# LitVP-02.net
KiCad netlist of a schematic drawn in Altium Designer
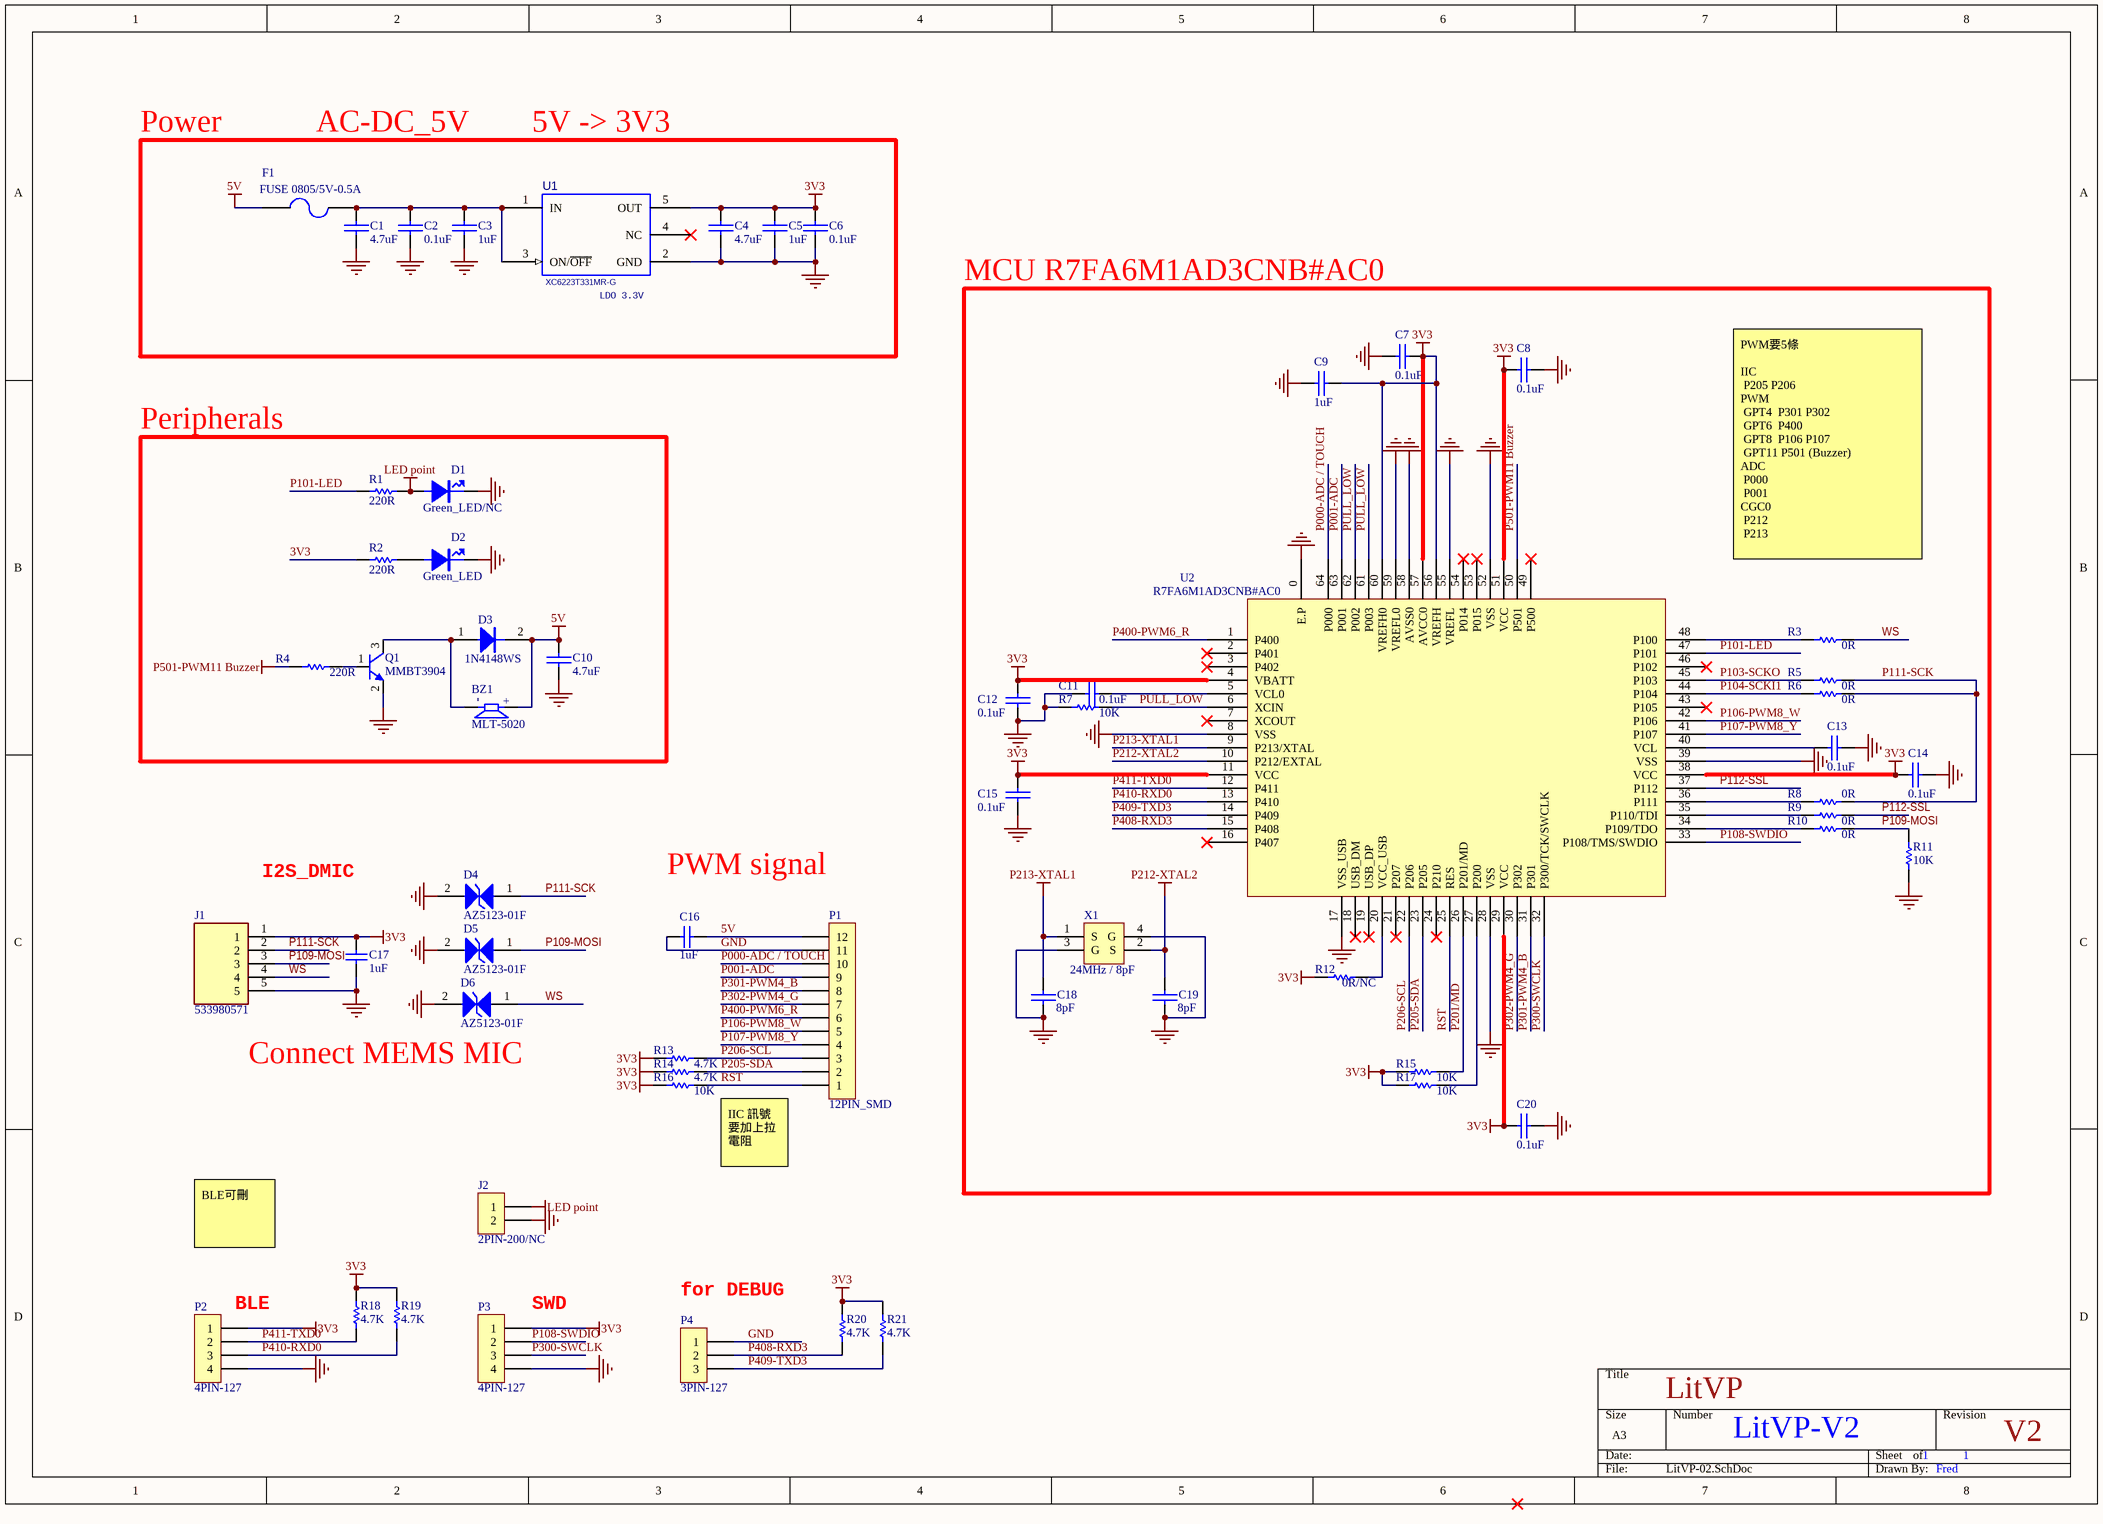
[diagram p0: LitVP-02.SchDoc]

(export (version "E")
  (design (tool "Eeschema 10.0.6"))
  (components
    (comp (ref "BZ1")
      (value "MLT-5020")
      (footprint "BUZZER-SMD-5*5mm")
      (description "Buzzer")
      (libsource (lib "*") (part "YZ5020CS-03L-4.0-12-R"))
    )
    (comp (ref "C1")
      (value "4.7uF")
      (footprint "QUAN:0402C")
      (description "Capacitor")
      (libsource (lib "CAP") (part "CAP"))
    )
    (comp (ref "C2")
      (value "0.1uF")
      (footprint "QUAN:0402C")
      (description "Capacitor")
      (libsource (lib "CAP") (part "CAP"))
    )
    (comp (ref "C3")
      (value "1uF")
      (footprint "QUAN:0402C")
      (description "Capacitor")
      (libsource (lib "CAP") (part "CAP"))
    )
    (comp (ref "C4")
      (value "4.7uF")
      (footprint "QUAN:0402C")
      (description "Capacitor")
      (libsource (lib "CAP") (part "CAP"))
    )
    (comp (ref "C5")
      (value "1uF")
      (footprint "QUAN:0402C")
      (description "Capacitor")
      (libsource (lib "CAP") (part "CAP"))
    )
    (comp (ref "C6")
      (value "0.1uF")
      (footprint "QUAN:0402C")
      (description "Capacitor")
      (libsource (lib "CAP") (part "CAP"))
    )
    (comp (ref "C7")
      (value "0.1uF")
      (footprint "QUAN:0402C")
      (description "Capacitor")
      (libsource (lib "CAP") (part "CAP"))
    )
    (comp (ref "C8")
      (value "0.1uF")
      (footprint "QUAN:0402C")
      (description "Capacitor")
      (libsource (lib "CAP") (part "CAP"))
    )
    (comp (ref "C9")
      (value "1uF")
      (footprint "QUAN:0402C")
      (description "Capacitor")
      (libsource (lib "CAP") (part "CAP"))
    )
    (comp (ref "C10")
      (value "4.7uF")
      (footprint "QUAN:0402C")
      (description "Capacitor")
      (libsource (lib "CAP") (part "CAP"))
    )
    (comp (ref "C11")
      (value "0.1uF")
      (footprint "QUAN:0402C")
      (description "Capacitor")
      (libsource (lib "CAP") (part "CAP"))
    )
    (comp (ref "C12")
      (value "0.1uF")
      (footprint "QUAN:0402C")
      (description "Capacitor")
      (libsource (lib "CAP") (part "CAP"))
    )
    (comp (ref "C13")
      (value "0.1uF")
      (footprint "QUAN:0402C")
      (description "Capacitor")
      (libsource (lib "CAP") (part "CAP"))
    )
    (comp (ref "C14")
      (value "0.1uF")
      (footprint "QUAN:0402C")
      (description "Capacitor")
      (libsource (lib "CAP") (part "CAP"))
    )
    (comp (ref "C15")
      (value "0.1uF")
      (footprint "QUAN:0402C")
      (description "Capacitor")
      (libsource (lib "CAP") (part "CAP"))
    )
    (comp (ref "C16")
      (value "1uF")
      (footprint "QUAN:0402C")
      (description "Capacitor")
      (libsource (lib "*") (part "Cap Semi"))
    )
    (comp (ref "C17")
      (value "1uF")
      (footprint "QUAN:0402C")
      (description "Capacitor")
      (libsource (lib "*") (part "Cap Semi"))
    )
    (comp (ref "C18")
      (value "8pF")
      (footprint "QUAN:0402C")
      (description "Capacitor")
      (libsource (lib "*") (part "CAP"))
    )
    (comp (ref "C19")
      (value "8pF")
      (footprint "QUAN:0402C")
      (description "Capacitor")
      (libsource (lib "*") (part "CAP"))
    )
    (comp (ref "C20")
      (value "0.1uF")
      (footprint "QUAN:0402C")
      (description "Capacitor")
      (libsource (lib "CAP") (part "CAP"))
    )
    (comp (ref "D1")
      (value "Green_LED/NC")
      (footprint "LED0603--0.4mm")
      (fields
        (field (name "MANUFACTURER'S PART NUMBER") "CL-170G-CD-T")
        (field (name "PART NUMBER") "41100017000")
        (field (name "MANUFACTURER") "Citizen")
      )
      (libsource (lib "*") (part "LED"))
    )
    (comp (ref "D2")
      (value "Green_LED")
      (footprint "LED0603--0.4mm")
      (fields
        (field (name "MANUFACTURER'S PART NUMBER") "CL-170G-CD-T")
        (field (name "PART NUMBER") "41100017000")
        (field (name "MANUFACTURER") "Citizen")
      )
      (libsource (lib "*") (part "LED"))
    )
    (comp (ref "D3")
      (value "1N4148WS")
      (footprint "SOD323-1N4148WS - pig pad")
      (libsource (lib "*") (part "DIODE"))
    )
    (comp (ref "D4")
      (value "AZ5123-01F")
      (footprint "LitVP-02:DIODE-0402")
      (description "ESD")
      (libsource (lib "*") (part "PESD5V0L1BA"))
    )
    (comp (ref "D5")
      (value "AZ5123-01F")
      (footprint "DIODE-0402")
      (description "ESD")
      (libsource (lib "*") (part "PESD5V0L1BA"))
    )
    (comp (ref "D6")
      (value "AZ5123-01F")
      (footprint "DIODE-0402")
      (description "ESD")
      (libsource (lib "*") (part "PESD5V0L1BA"))
    )
    (comp (ref "F1")
      (value "FUSE 0805/5V-0.5A")
      (footprint "QUAN:0805_FUSE")
      (description "Fuse")
      (libsource (lib "*") (part "FUSE2"))
    )
    (comp (ref "J1")
      (value "533980571")
      (footprint "SamacSys:53398-0571")
      (description "Connector")
      (fields (field (name "MANUFACTURER_PART_NUMBER") "53048-0510"))
      (libsource (lib "*") (part "53048-0510"))
    )
    (comp (ref "J2")
      (value "2PIN-200/NC")
      (footprint "2PIN-127")
      (description "Connector")
      (libsource (lib "PIN") (part "2PIN-200"))
    )
    (comp (ref "P1")
      (value "12PIN_SMD")
      (footprint "QUAN:12PIN_SAMTEC-MMT-136-02-X-SH")
      (libsource (lib "PIN") (part "12PIN_SMD"))
    )
    (comp (ref "P2")
      (value "4PIN-127")
      (footprint "QUAN:4PIN-127_0.85_0.505")
      (description "1.27mm Header")
      (libsource (lib "*") (part "CON4"))
    )
    (comp (ref "P3")
      (value "4PIN-127")
      (footprint "QUAN:4PIN-127_0.85_0.505")
      (description "1.27mm Header")
      (libsource (lib "*") (part "CON4"))
    )
    (comp (ref "P4") (value "3PIN-127") (footprint "QUAN:3PIN-127") (libsource (lib "PIN") (part "3PIN-127")))
    (comp (ref "Q1")
      (value "MMBT3904")
      (footprint "QUAN:SOT-23")
      (description "NPN General Purpose Amplifier")
      (fields (field (name "PUBLISHER") "*"))
      (libsource (lib "*") (part "NPN-3"))
    )
    (comp (ref "R1")
      (value "220R")
      (footprint "QUAN:0402")
      (description "Resistor")
      (libsource (lib "*") (part "Res Semi"))
    )
    (comp (ref "R2")
      (value "220R")
      (footprint "QUAN:0402")
      (description "Resistor")
      (libsource (lib "*") (part "Res Semi"))
    )
    (comp (ref "R3")
      (value "0R")
      (footprint "QUAN:0402")
      (description "Resistor")
      (libsource (lib "*") (part "Res Semi"))
    )
    (comp (ref "R4")
      (value "220R")
      (footprint "QUAN:0402")
      (description "Resistor")
      (libsource (lib "*") (part "Res Semi"))
    )
    (comp (ref "R5")
      (value "0R")
      (footprint "QUAN:0402")
      (description "Resistor")
      (libsource (lib "*") (part "Res Semi"))
    )
    (comp (ref "R6")
      (value "0R")
      (footprint "QUAN:0402")
      (description "Resistor")
      (libsource (lib "*") (part "Res Semi"))
    )
    (comp (ref "R7")
      (value "10K")
      (footprint "QUAN:0402")
      (description "Resistor")
      (libsource (lib "*") (part "Res Semi"))
    )
    (comp (ref "R8")
      (value "0R")
      (footprint "QUAN:0402")
      (description "Resistor")
      (libsource (lib "*") (part "Res Semi"))
    )
    (comp (ref "R9")
      (value "0R")
      (footprint "QUAN:0402")
      (description "Resistor")
      (libsource (lib "*") (part "Res Semi"))
    )
    (comp (ref "R10")
      (value "0R")
      (footprint "QUAN:0402")
      (description "Resistor")
      (libsource (lib "*") (part "Res Semi"))
    )
    (comp (ref "R11")
      (value "10K")
      (footprint "QUAN:0402")
      (description "Resistor")
      (libsource (lib "*") (part "Res Semi"))
    )
    (comp (ref "R12")
      (value "0R/NC")
      (footprint "QUAN:0402")
      (description "Resistor")
      (libsource (lib "*") (part "Res Semi"))
    )
    (comp (ref "R13")
      (value "4.7K")
      (footprint "QUAN:0402")
      (description "Resistor")
      (libsource (lib "*") (part "Res Semi"))
    )
    (comp (ref "R14")
      (value "4.7K")
      (footprint "QUAN:0402")
      (description "Resistor")
      (libsource (lib "*") (part "Res Semi"))
    )
    (comp (ref "R15")
      (value "10K")
      (footprint "QUAN:0402")
      (description "Resistor")
      (libsource (lib "*") (part "Res Semi"))
    )
    (comp (ref "R16")
      (value "10K")
      (footprint "QUAN:0402")
      (description "Resistor")
      (libsource (lib "*") (part "Res Semi"))
    )
    (comp (ref "R17")
      (value "10K")
      (footprint "QUAN:0402")
      (description "Resistor")
      (libsource (lib "*") (part "Res Semi"))
    )
    (comp (ref "R18")
      (value "4.7K")
      (footprint "QUAN:0402")
      (description "Resistor")
      (libsource (lib "*") (part "Res Semi"))
    )
    (comp (ref "R19")
      (value "4.7K")
      (footprint "QUAN:0402")
      (description "Resistor")
      (libsource (lib "*") (part "Res Semi"))
    )
    (comp (ref "R20")
      (value "4.7K")
      (footprint "QUAN:0402")
      (description "Resistor")
      (libsource (lib "*") (part "Res Semi"))
    )
    (comp (ref "R21")
      (value "4.7K")
      (footprint "QUAN:0402")
      (description "Resistor")
      (libsource (lib "*") (part "Res Semi"))
    )
    (comp (ref "U1")
      (value "XC6223T331MR-G")
      (footprint "SOT-23-5-0.95MM")
      (libsource (lib "*") (part "XC6223T331MR-G"))
    )
    (comp (ref "U2")
      (value "R7FA6M1AD3CNB#AC0")
      (footprint "QFN64-0.4mm-8X8")
      (description "MCU")
      (libsource (lib "*") (part "R7FA6M1AD3CNB#AC0"))
    )
    (comp (ref "X1")
      (value "24MHz / 8pF")
      (footprint "XTAL-SMD-20X16")
      (libsource (lib "*") (part "XTAL-SMD-25*32"))
    )
  )
  (nets
    (net (code "1") (name "/P000-ADC {slash} TOUCH") (class "Default")
      (node (ref "P1") (pin "10") (pinfunction "10_10") (pintype "passive"))
      (node (ref "U2") (pin "64") (pinfunction "P000_64") (pintype "passive"))
    )
    (net (code "2") (name "/P001-ADC") (class "Default")
      (node (ref "P1") (pin "9") (pinfunction "9_9") (pintype "passive"))
      (node (ref "U2") (pin "63") (pinfunction "P001_63") (pintype "passive"))
    )
    (net (code "3") (name "/P101-LED") (class "Default")
      (node (ref "R1") (pin "1") (pinfunction "1_1") (pintype "passive"))
      (node (ref "U2") (pin "47") (pinfunction "P101_47") (pintype "passive"))
    )
    (net (code "4") (name "/P103-SCKO") (class "Default")
      (node (ref "R5") (pin "2") (pinfunction "2_2") (pintype "passive"))
      (node (ref "U2") (pin "45") (pinfunction "P103_45") (pintype "passive"))
    )
    (net (code "5") (name "/P104-SCKI1") (class "Default")
      (node (ref "R6") (pin "2") (pinfunction "2_2") (pintype "passive"))
      (node (ref "U2") (pin "44") (pinfunction "P104_44") (pintype "passive"))
    )
    (net (code "6") (name "/P106-PWM8_W") (class "Default")
      (node (ref "P1") (pin "5") (pinfunction "5_5") (pintype "passive"))
      (node (ref "U2") (pin "42") (pinfunction "P106_42") (pintype "passive"))
    )
    (net (code "7") (name "/P107-PWM8_Y") (class "Default")
      (node (ref "P1") (pin "4") (pinfunction "4_4") (pintype "passive"))
      (node (ref "U2") (pin "41") (pinfunction "P107_41") (pintype "passive"))
    )
    (net (code "8") (name "/P108-SWDIO") (class "Default")
      (node (ref "P3") (pin "2") (pinfunction "2_2") (pintype "passive"))
      (node (ref "U2") (pin "33") (pinfunction "P108/TMS/SWDIO_33") (pintype "passive"))
    )
    (net (code "9") (name "/P109-MOSI") (class "Default")
      (node (ref "D5") (pin "1") (pinfunction "1_1") (pintype "passive"))
      (node (ref "J1") (pin "3") (pinfunction "3_3") (pintype "passive"))
      (node (ref "R10") (pin "1") (pinfunction "1_1") (pintype "passive"))
      (node (ref "R11") (pin "2") (pinfunction "2_2") (pintype "passive"))
    )
    (net (code "10") (name "/P111-SCK") (class "Default")
      (node (ref "D4") (pin "1") (pinfunction "1_1") (pintype "passive"))
      (node (ref "J1") (pin "2") (pinfunction "2_2") (pintype "passive"))
      (node (ref "R5") (pin "1") (pinfunction "1_1") (pintype "passive"))
      (node (ref "R6") (pin "1") (pinfunction "1_1") (pintype "passive"))
      (node (ref "R8") (pin "1") (pinfunction "1_1") (pintype "passive"))
    )
    (net (code "11") (name "/P112-SSL") (class "Default")
      (node (ref "R9") (pin "1") (pinfunction "1_1") (pintype "passive"))
      (node (ref "U2") (pin "37") (pinfunction "P112_37") (pintype "passive"))
    )
    (net (code "12") (name "/P201{slash}MD") (class "Default")
      (node (ref "R15") (pin "1") (pinfunction "1_1") (pintype "passive"))
      (node (ref "U2") (pin "26") (pinfunction "P201/MD_26") (pintype "passive"))
    )
    (net (code "13") (name "/P205-SDA") (class "Default")
      (node (ref "P1") (pin "2") (pinfunction "2_2") (pintype "passive"))
      (node (ref "R14") (pin "1") (pinfunction "1_1") (pintype "passive"))
      (node (ref "U2") (pin "23") (pinfunction "P205_23") (pintype "passive"))
    )
    (net (code "14") (name "/P206-SCL") (class "Default")
      (node (ref "P1") (pin "3") (pinfunction "3_3") (pintype "passive"))
      (node (ref "R13") (pin "1") (pinfunction "1_1") (pintype "passive"))
      (node (ref "U2") (pin "22") (pinfunction "P206_22") (pintype "passive"))
    )
    (net (code "15") (name "/P300-SWCLK") (class "Default")
      (node (ref "P3") (pin "3") (pinfunction "3_3") (pintype "passive"))
      (node (ref "U2") (pin "32") (pinfunction "P300/TCK/SWCLK_32") (pintype "passive"))
    )
    (net (code "16") (name "/P301-PWM4_B") (class "Default")
      (node (ref "P1") (pin "8") (pinfunction "8_8") (pintype "passive"))
      (node (ref "U2") (pin "31") (pinfunction "P301_31") (pintype "passive"))
    )
    (net (code "17") (name "/P302-PWM4_G") (class "Default")
      (node (ref "P1") (pin "7") (pinfunction "7_7") (pintype "passive"))
      (node (ref "U2") (pin "30") (pinfunction "P302_30") (pintype "passive"))
    )
    (net (code "18") (name "/P400-PWM6_R") (class "Default")
      (node (ref "P1") (pin "6") (pinfunction "6_6") (pintype "passive"))
      (node (ref "U2") (pin "1") (pinfunction "P400_1") (pintype "passive"))
    )
    (net (code "19") (name "/P408-RXD3") (class "Default")
      (node (ref "P4") (pin "2") (pinfunction "2_2") (pintype "passive"))
      (node (ref "R20") (pin "2") (pinfunction "2_2") (pintype "passive"))
      (node (ref "U2") (pin "15") (pinfunction "P408_15") (pintype "passive"))
    )
    (net (code "20") (name "/P409-TXD3") (class "Default")
      (node (ref "P4") (pin "3") (pinfunction "3_3") (pintype "passive"))
      (node (ref "R21") (pin "2") (pinfunction "2_2") (pintype "passive"))
      (node (ref "U2") (pin "14") (pinfunction "P409_14") (pintype "passive"))
    )
    (net (code "21") (name "/P410-RXD0") (class "Default")
      (node (ref "P2") (pin "3") (pinfunction "3_3") (pintype "passive"))
      (node (ref "R19") (pin "2") (pinfunction "2_2") (pintype "passive"))
      (node (ref "U2") (pin "13") (pinfunction "P410_13") (pintype "passive"))
    )
    (net (code "22") (name "/P411-TXD0") (class "Default")
      (node (ref "P2") (pin "2") (pinfunction "2_2") (pintype "passive"))
      (node (ref "R18") (pin "2") (pinfunction "2_2") (pintype "passive"))
      (node (ref "U2") (pin "12") (pinfunction "P411_12") (pintype "passive"))
    )
    (net (code "23") (name "/PULL_LOW") (class "Default")
      (node (ref "R7") (pin "1") (pinfunction "1_1") (pintype "passive"))
      (node (ref "U2") (pin "6") (pinfunction "XCIN_6") (pintype "passive"))
      (node (ref "U2") (pin "61") (pinfunction "P003_61") (pintype "passive"))
      (node (ref "U2") (pin "62") (pinfunction "P002_62") (pintype "passive"))
    )
    (net (code "24") (name "/RST") (class "Default")
      (node (ref "P1") (pin "1") (pinfunction "1_1") (pintype "passive"))
      (node (ref "R16") (pin "1") (pinfunction "1_1") (pintype "passive"))
      (node (ref "U2") (pin "25") (pinfunction "RES_25") (pintype "passive"))
    )
    (net (code "25") (name "/WS") (class "Default")
      (node (ref "D6") (pin "1") (pinfunction "1_1") (pintype "passive"))
      (node (ref "J1") (pin "4") (pinfunction "4_4") (pintype "passive"))
      (node (ref "R3") (pin "1") (pinfunction "1_1") (pintype "passive"))
    )
    (net (code "26") (name "3V3") (class "Default")
      (node (ref "C12") (pin "2") (pinfunction "2_2") (pintype "passive"))
      (node (ref "C14") (pin "2") (pinfunction "2_2") (pintype "passive"))
      (node (ref "C15") (pin "2") (pinfunction "2_2") (pintype "passive"))
      (node (ref "C17") (pin "2") (pinfunction "2_2") (pintype "passive"))
      (node (ref "C20") (pin "2") (pinfunction "2_2") (pintype "passive"))
      (node (ref "C4") (pin "1") (pinfunction "1_1") (pintype "passive"))
      (node (ref "C5") (pin "1") (pinfunction "1_1") (pintype "passive"))
      (node (ref "C6") (pin "1") (pinfunction "1_1") (pintype "passive"))
      (node (ref "C7") (pin "2") (pinfunction "2_2") (pintype "passive"))
      (node (ref "C8") (pin "1") (pinfunction "1_1") (pintype "passive"))
      (node (ref "C9") (pin "2") (pinfunction "2_2") (pintype "passive"))
      (node (ref "J1") (pin "1") (pinfunction "1_1") (pintype "passive"))
      (node (ref "P2") (pin "1") (pinfunction "1_1") (pintype "passive"))
      (node (ref "P3") (pin "1") (pinfunction "1_1") (pintype "passive"))
      (node (ref "R12") (pin "2") (pinfunction "2_2") (pintype "passive"))
      (node (ref "R13") (pin "2") (pinfunction "2_2") (pintype "passive"))
      (node (ref "R14") (pin "2") (pinfunction "2_2") (pintype "passive"))
      (node (ref "R15") (pin "2") (pinfunction "2_2") (pintype "passive"))
      (node (ref "R16") (pin "2") (pinfunction "2_2") (pintype "passive"))
      (node (ref "R17") (pin "2") (pinfunction "2_2") (pintype "passive"))
      (node (ref "R18") (pin "1") (pinfunction "1_1") (pintype "passive"))
      (node (ref "R19") (pin "1") (pinfunction "1_1") (pintype "passive"))
      (node (ref "R2") (pin "1") (pinfunction "1_1") (pintype "passive"))
      (node (ref "R20") (pin "1") (pinfunction "1_1") (pintype "passive"))
      (node (ref "R21") (pin "1") (pinfunction "1_1") (pintype "passive"))
      (node (ref "U1") (pin "5") (pinfunction "OUT_5") (pintype "passive"))
      (node (ref "U2") (pin "11") (pinfunction "VCC_11") (pintype "passive"))
      (node (ref "U2") (pin "29") (pinfunction "VCC_29") (pintype "passive"))
      (node (ref "U2") (pin "38") (pinfunction "VCC_38") (pintype "passive"))
      (node (ref "U2") (pin "4") (pinfunction "VBATT_4") (pintype "passive"))
      (node (ref "U2") (pin "51") (pinfunction "VCC_51") (pintype "passive"))
      (node (ref "U2") (pin "56") (pinfunction "VREFH_56") (pintype "passive"))
      (node (ref "U2") (pin "57") (pinfunction "AVCC0_57") (pintype "passive"))
      (node (ref "U2") (pin "60") (pinfunction "VREFH0_60") (pintype "passive"))
    )
    (net (code "27") (name "5V") (class "Default")
      (node (ref "BZ1") (pin "1") (pinfunction "1_1") (pintype "passive"))
      (node (ref "C10") (pin "1") (pinfunction "1_1") (pintype "passive"))
      (node (ref "C16") (pin "1") (pinfunction "1_1") (pintype "passive"))
      (node (ref "D3") (pin "2") (pinfunction "2_2") (pintype "passive"))
      (node (ref "F1") (pin "1") (pinfunction "1_1") (pintype "passive"))
      (node (ref "P1") (pin "12") (pinfunction "12_12") (pintype "passive"))
    )
    (net (code "28") (name "GND") (class "Default")
      (node (ref "C1") (pin "2") (pinfunction "2_2") (pintype "passive"))
      (node (ref "C10") (pin "2") (pinfunction "2_2") (pintype "passive"))
      (node (ref "C11") (pin "2") (pinfunction "2_2") (pintype "passive"))
      (node (ref "C12") (pin "1") (pinfunction "1_1") (pintype "passive"))
      (node (ref "C13") (pin "1") (pinfunction "1_1") (pintype "passive"))
      (node (ref "C14") (pin "1") (pinfunction "1_1") (pintype "passive"))
      (node (ref "C15") (pin "1") (pinfunction "1_1") (pintype "passive"))
      (node (ref "C16") (pin "2") (pinfunction "2_2") (pintype "passive"))
      (node (ref "C17") (pin "1") (pinfunction "1_1") (pintype "passive"))
      (node (ref "C18") (pin "2") (pinfunction "2_2") (pintype "passive"))
      (node (ref "C19") (pin "2") (pinfunction "2_2") (pintype "passive"))
      (node (ref "C2") (pin "2") (pinfunction "2_2") (pintype "passive"))
      (node (ref "C20") (pin "1") (pinfunction "1_1") (pintype "passive"))
      (node (ref "C3") (pin "2") (pinfunction "2_2") (pintype "passive"))
      (node (ref "C4") (pin "2") (pinfunction "2_2") (pintype "passive"))
      (node (ref "C5") (pin "2") (pinfunction "2_2") (pintype "passive"))
      (node (ref "C6") (pin "2") (pinfunction "2_2") (pintype "passive"))
      (node (ref "C7") (pin "1") (pinfunction "1_1") (pintype "passive"))
      (node (ref "C8") (pin "2") (pinfunction "2_2") (pintype "passive"))
      (node (ref "C9") (pin "1") (pinfunction "1_1") (pintype "passive"))
      (node (ref "D1") (pin "2") (pinfunction "2_2") (pintype "passive"))
      (node (ref "D2") (pin "2") (pinfunction "2_2") (pintype "passive"))
      (node (ref "D4") (pin "2") (pinfunction "2_2") (pintype "passive"))
      (node (ref "D5") (pin "2") (pinfunction "2_2") (pintype "passive"))
      (node (ref "D6") (pin "2") (pinfunction "2_2") (pintype "passive"))
      (node (ref "J1") (pin "5") (pinfunction "5_5") (pintype "passive"))
      (node (ref "J2") (pin "2") (pinfunction "2_2") (pintype "passive"))
      (node (ref "P1") (pin "11") (pinfunction "11_11") (pintype "passive"))
      (node (ref "P2") (pin "4") (pinfunction "4_4") (pintype "passive"))
      (node (ref "P3") (pin "4") (pinfunction "4_4") (pintype "passive"))
      (node (ref "P4") (pin "1") (pinfunction "1_1") (pintype "passive"))
      (node (ref "Q1") (pin "2") (pinfunction "E_2") (pintype "passive"))
      (node (ref "R11") (pin "1") (pinfunction "1_1") (pintype "passive"))
      (node (ref "R7") (pin "2") (pinfunction "2_2") (pintype "passive"))
      (node (ref "U1") (pin "2") (pinfunction "GND_2") (pintype "passive"))
      (node (ref "U2") (pin "0") (pinfunction "E.P_0") (pintype "passive"))
      (node (ref "U2") (pin "17") (pinfunction "VSS_USB_17") (pintype "passive"))
      (node (ref "U2") (pin "28") (pinfunction "VSS_28") (pintype "passive"))
      (node (ref "U2") (pin "39") (pinfunction "VSS_39") (pintype "passive"))
      (node (ref "U2") (pin "52") (pinfunction "VSS_52") (pintype "passive"))
      (node (ref "U2") (pin "55") (pinfunction "VREFL_55") (pintype "passive"))
      (node (ref "U2") (pin "58") (pinfunction "AVSS0_58") (pintype "passive"))
      (node (ref "U2") (pin "59") (pinfunction "VREFL0_59") (pintype "passive"))
      (node (ref "U2") (pin "8") (pinfunction "VSS_8") (pintype "passive"))
      (node (ref "X1") (pin "3") (pinfunction "G_3") (pintype "passive"))
      (node (ref "X1") (pin "4") (pinfunction "G_4") (pintype "passive"))
    )
    (net (code "29") (name "LED point") (class "Default")
      (node (ref "D1") (pin "1") (pinfunction "1_1") (pintype "passive"))
      (node (ref "J2") (pin "1") (pinfunction "1_1") (pintype "passive"))
      (node (ref "R1") (pin "2") (pinfunction "2_2") (pintype "passive"))
    )
    (net (code "30") (name "Net-(D2-Pad1)") (class "Default")
      (node (ref "D2") (pin "1") (pinfunction "1_1") (pintype "passive"))
      (node (ref "R2") (pin "2") (pinfunction "2_2") (pintype "passive"))
    )
    (net (code "31") (name "Net-(Q1-B)") (class "Default")
      (node (ref "Q1") (pin "1") (pinfunction "B_1") (pintype "passive"))
      (node (ref "R4") (pin "1") (pinfunction "1_1") (pintype "passive"))
    )
    (net (code "32") (name "Net-(Q1-C)") (class "Default")
      (node (ref "BZ1") (pin "2") (pinfunction "2_2") (pintype "passive"))
      (node (ref "D3") (pin "1") (pinfunction "1_1") (pintype "passive"))
      (node (ref "Q1") (pin "3") (pinfunction "C_3") (pintype "passive"))
    )
    (net (code "33") (name "Net-(U1-IN)") (class "Default")
      (node (ref "C1") (pin "1") (pinfunction "1_1") (pintype "passive"))
      (node (ref "C2") (pin "1") (pinfunction "1_1") (pintype "passive"))
      (node (ref "C3") (pin "1") (pinfunction "1_1") (pintype "passive"))
      (node (ref "F1") (pin "2") (pinfunction "2_2") (pintype "passive"))
      (node (ref "U1") (pin "1") (pinfunction "IN_1") (pintype "passive"))
      (node (ref "U1") (pin "3") (pinfunction "ON/~{OFF}_3") (pintype "input"))
    )
    (net (code "34") (name "Net-(U2-P100)") (class "Default")
      (node (ref "R3") (pin "2") (pinfunction "2_2") (pintype "passive"))
      (node (ref "U2") (pin "48") (pinfunction "P100_48") (pintype "passive"))
    )
    (net (code "35") (name "Net-(U2-P109{slash}TDO)") (class "Default")
      (node (ref "R10") (pin "2") (pinfunction "2_2") (pintype "passive"))
      (node (ref "U2") (pin "34") (pinfunction "P109/TDO_34") (pintype "passive"))
    )
    (net (code "36") (name "Net-(U2-P110{slash}TDI)") (class "Default")
      (node (ref "R9") (pin "2") (pinfunction "2_2") (pintype "passive"))
      (node (ref "U2") (pin "35") (pinfunction "P110/TDI_35") (pintype "passive"))
    )
    (net (code "37") (name "Net-(U2-P111)") (class "Default")
      (node (ref "R8") (pin "2") (pinfunction "2_2") (pintype "passive"))
      (node (ref "U2") (pin "36") (pinfunction "P111_36") (pintype "passive"))
    )
    (net (code "38") (name "Net-(U2-P200)") (class "Default")
      (node (ref "R17") (pin "1") (pinfunction "1_1") (pintype "passive"))
      (node (ref "U2") (pin "27") (pinfunction "P200_27") (pintype "passive"))
    )
    (net (code "39") (name "Net-(U2-VCC_USB)") (class "Default")
      (node (ref "R12") (pin "1") (pinfunction "1_1") (pintype "passive"))
      (node (ref "U2") (pin "20") (pinfunction "VCC_USB_20") (pintype "passive"))
    )
    (net (code "40") (name "Net-(U2-VCL)") (class "Default")
      (node (ref "C13") (pin "2") (pinfunction "2_2") (pintype "passive"))
      (node (ref "U2") (pin "40") (pinfunction "VCL_40") (pintype "passive"))
    )
    (net (code "41") (name "Net-(U2-VCL0)") (class "Default")
      (node (ref "C11") (pin "1") (pinfunction "1_1") (pintype "passive"))
      (node (ref "U2") (pin "5") (pinfunction "VCL0_5") (pintype "passive"))
    )
    (net (code "42") (name "P212-XTAL2") (class "Default")
      (node (ref "C19") (pin "1") (pinfunction "1_1") (pintype "passive"))
      (node (ref "U2") (pin "10") (pinfunction "P212/EXTAL_10") (pintype "passive"))
      (node (ref "X1") (pin "2") (pinfunction "S_2") (pintype "passive"))
    )
    (net (code "43") (name "P213-XTAL1") (class "Default")
      (node (ref "C18") (pin "1") (pinfunction "1_1") (pintype "passive"))
      (node (ref "U2") (pin "9") (pinfunction "P213/XTAL_9") (pintype "passive"))
      (node (ref "X1") (pin "1") (pinfunction "S_1") (pintype "passive"))
    )
    (net (code "44") (name "P501-PWM11 Buzzer") (class "Default")
      (node (ref "R4") (pin "2") (pinfunction "2_2") (pintype "passive"))
      (node (ref "U2") (pin "50") (pinfunction "P501_50") (pintype "passive"))
    )
    (net (code "45") (name "unconnected-(U1-NC-Pad4)") (class "Default")
      (node (ref "U1") (pin "4") (pinfunction "NC_4") (pintype "passive+no_connect"))
    )
    (net (code "46") (name "unconnected-(U2-P014-Pad54)") (class "Default")
      (node (ref "U2") (pin "54") (pinfunction "P014_54") (pintype "passive+no_connect"))
    )
    (net (code "47") (name "unconnected-(U2-P015-Pad53)") (class "Default")
      (node (ref "U2") (pin "53") (pinfunction "P015_53") (pintype "passive+no_connect"))
    )
    (net (code "48") (name "unconnected-(U2-P102-Pad46)") (class "Default")
      (node (ref "U2") (pin "46") (pinfunction "P102_46") (pintype "passive+no_connect"))
    )
    (net (code "49") (name "unconnected-(U2-P105-Pad43)") (class "Default")
      (node (ref "U2") (pin "43") (pinfunction "P105_43") (pintype "passive+no_connect"))
    )
    (net (code "50") (name "unconnected-(U2-P207-Pad21)") (class "Default")
      (node (ref "U2") (pin "21") (pinfunction "P207_21") (pintype "passive+no_connect"))
    )
    (net (code "51") (name "unconnected-(U2-P210-Pad24)") (class "Default")
      (node (ref "U2") (pin "24") (pinfunction "P210_24") (pintype "passive+no_connect"))
    )
    (net (code "52") (name "unconnected-(U2-P401-Pad2)") (class "Default")
      (node (ref "U2") (pin "2") (pinfunction "P401_2") (pintype "passive+no_connect"))
    )
    (net (code "53") (name "unconnected-(U2-P402-Pad3)") (class "Default")
      (node (ref "U2") (pin "3") (pinfunction "P402_3") (pintype "passive+no_connect"))
    )
    (net (code "54") (name "unconnected-(U2-P407-Pad16)") (class "Default")
      (node (ref "U2") (pin "16") (pinfunction "P407_16") (pintype "passive+no_connect"))
    )
    (net (code "55") (name "unconnected-(U2-P500-Pad49)") (class "Default")
      (node (ref "U2") (pin "49") (pinfunction "P500_49") (pintype "passive+no_connect"))
    )
    (net (code "56") (name "unconnected-(U2-USB_DM-Pad18)") (class "Default")
      (node (ref "U2") (pin "18") (pinfunction "USB_DM_18") (pintype "passive+no_connect"))
    )
    (net (code "57") (name "unconnected-(U2-USB_DP-Pad19)") (class "Default")
      (node (ref "U2") (pin "19") (pinfunction "USB_DP_19") (pintype "passive+no_connect"))
    )
    (net (code "58") (name "unconnected-(U2-XCOUT-Pad7)") (class "Default")
      (node (ref "U2") (pin "7") (pinfunction "XCOUT_7") (pintype "passive+no_connect"))
    )
  )
)
